# EbookReader.net
KiCad netlist of a schematic drawn in EAGLE
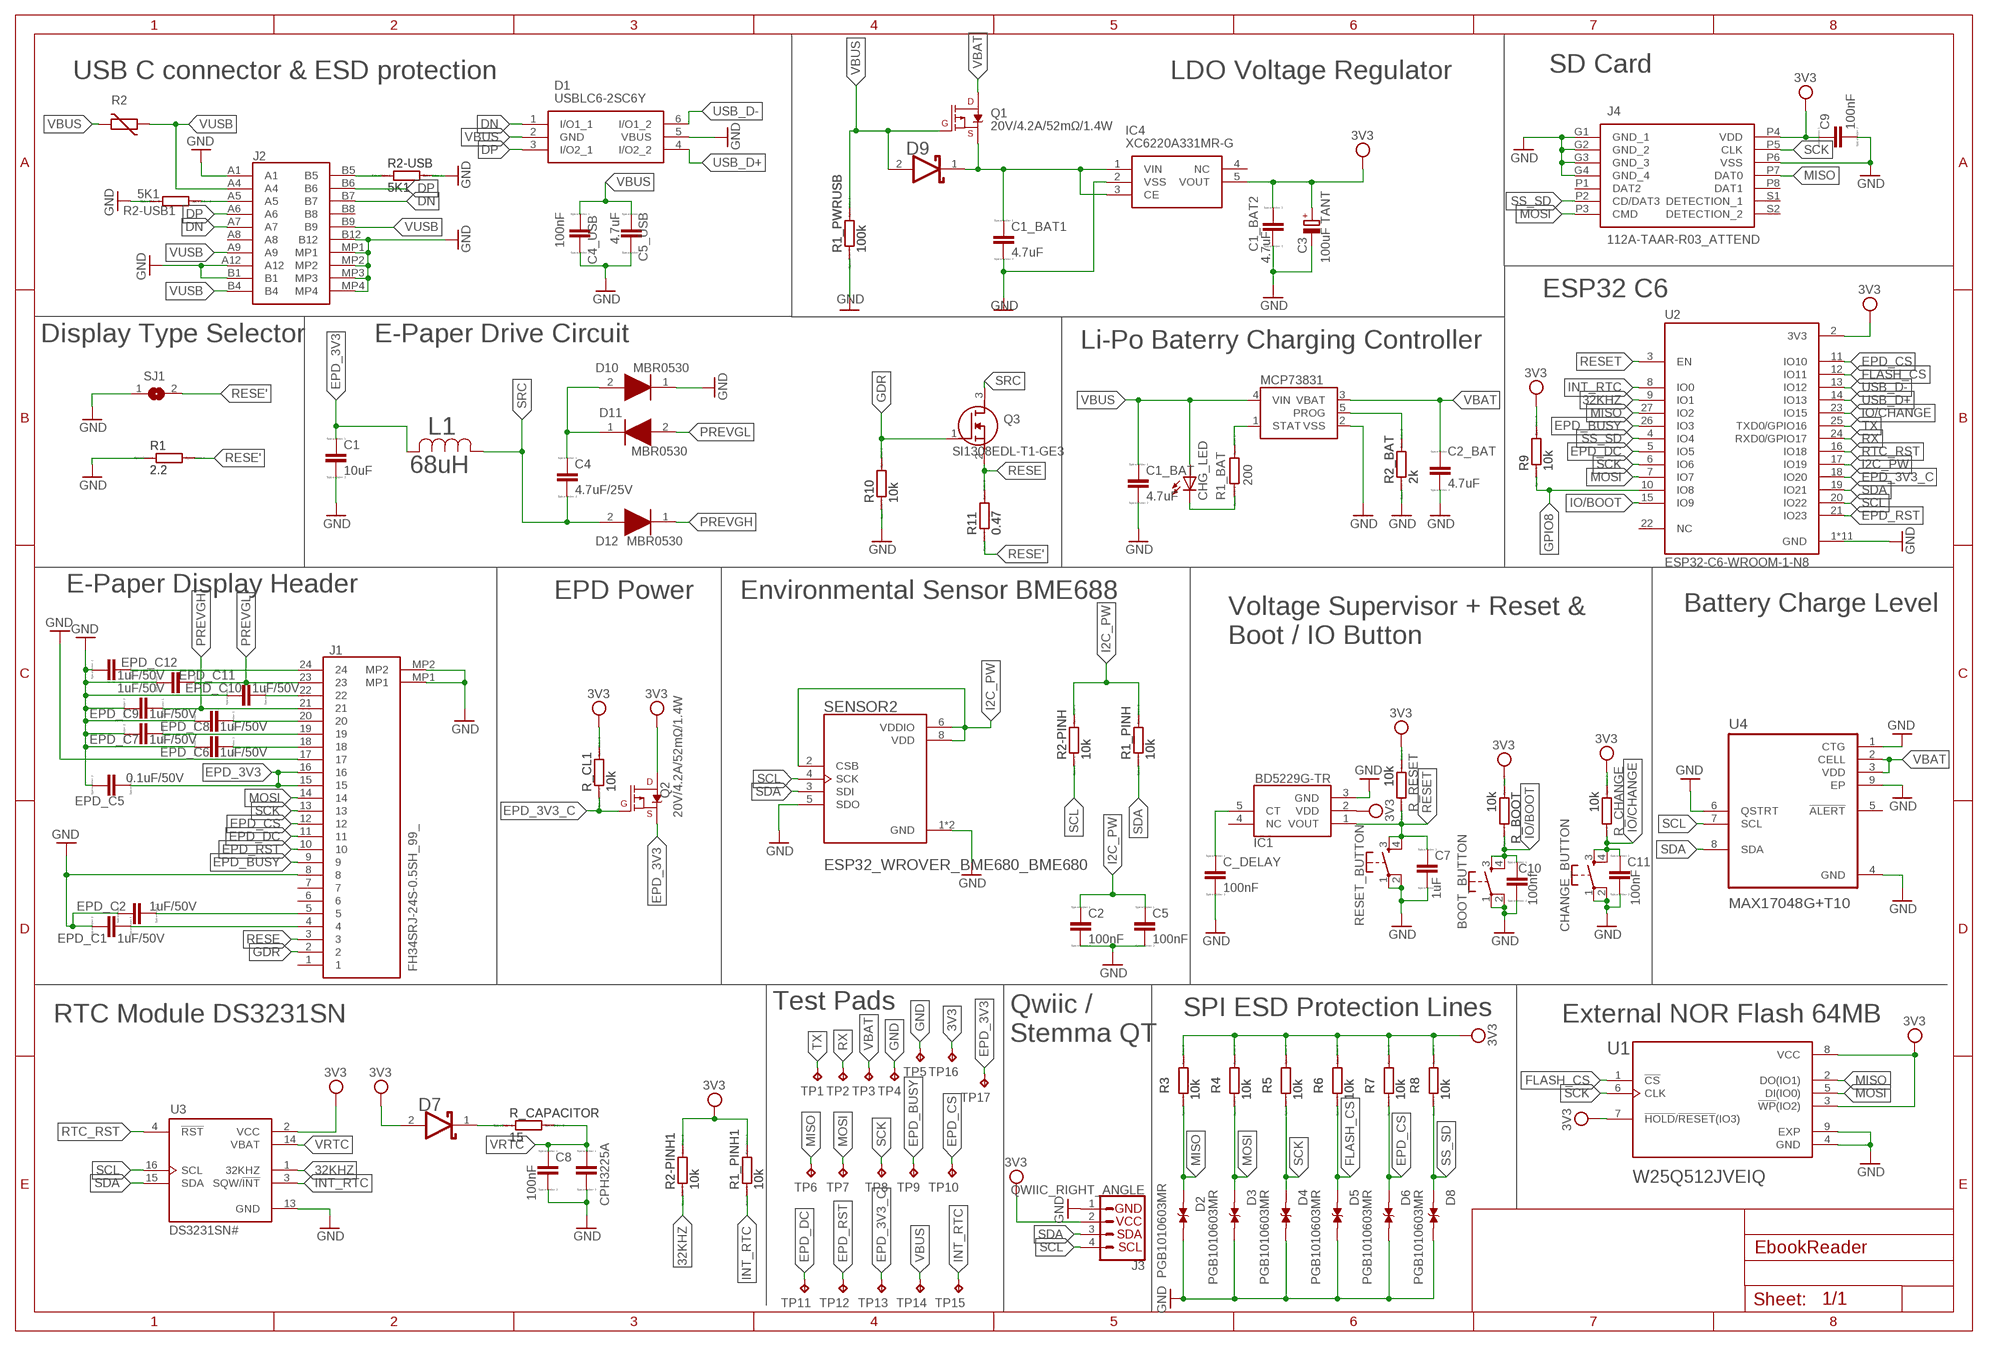
[diagram p0: schematic, sheet 1]

(export (version "E")
  (design (tool "Eeschema 10.0.6"))
  (components
    (comp (ref "BOOT_BUTTON")
      (value "BUTTON_CUSYOMV1")
      (footprint "eagle-import:MYBUTTON")
      (libsource (lib "eagle-import") (part "BUTTON_CUSYOMV1"))
    )
    (comp (ref "C1")
      (value "10uF")
      (footprint "eagle-import:ESP32_WROVER_EAGLE-LTSPICE_C0402")
      (libsource (lib "eagle-import") (part "ESP32_WROVER_EAGLE-LTSPICE_CC0402"))
    )
    (comp (ref "C1_BAT")
      (value "4.7uF")
      (footprint "eagle-import:ESP32_WROVER_EAGLE-LTSPICE_C0402")
      (libsource (lib "eagle-import") (part "ESP32_WROVER_EAGLE-LTSPICE_CC0402"))
    )
    (comp (ref "C1_BAT1")
      (value "4.7uF")
      (footprint "eagle-import:ESP32_WROVER_EAGLE-LTSPICE_C0402")
      (libsource (lib "eagle-import") (part "ESP32_WROVER_EAGLE-LTSPICE_CC0402"))
    )
    (comp (ref "C1_BAT2")
      (value "4.7uF")
      (footprint "eagle-import:ESP32_WROVER_EAGLE-LTSPICE_C0402")
      (libsource (lib "eagle-import") (part "ESP32_WROVER_EAGLE-LTSPICE_CC0402"))
    )
    (comp (ref "C2")
      (value "100nF")
      (footprint "eagle-import:ESP32_WROVER_EAGLE-LTSPICE_C0402")
      (libsource (lib "eagle-import") (part "ESP32_WROVER_EAGLE-LTSPICE_CC0402"))
    )
    (comp (ref "C2_BAT")
      (value "4.7uF")
      (footprint "eagle-import:ESP32_WROVER_EAGLE-LTSPICE_C0402")
      (libsource (lib "eagle-import") (part "ESP32_WROVER_EAGLE-LTSPICE_CC0402"))
    )
    (comp (ref "C3")
      (value "100uF TANT")
      (footprint "eagle-import:RCL_CT3528")
      (libsource (lib "eagle-import") (part "RCL_CPOL-EUCT3528"))
    )
    (comp (ref "C4")
      (value "4.7uF/25V")
      (footprint "eagle-import:ESP32_WROVER_EAGLE-LTSPICE_C0402")
      (libsource (lib "eagle-import") (part "ESP32_WROVER_EAGLE-LTSPICE_CC0402"))
    )
    (comp (ref "C4_USB")
      (value "100nF")
      (footprint "eagle-import:ESP32_WROVER_EAGLE-LTSPICE_C0402")
      (libsource (lib "eagle-import") (part "ESP32_WROVER_EAGLE-LTSPICE_CC0402"))
    )
    (comp (ref "C5")
      (value "100nF")
      (footprint "eagle-import:ESP32_WROVER_EAGLE-LTSPICE_C0402")
      (libsource (lib "eagle-import") (part "ESP32_WROVER_EAGLE-LTSPICE_CC0402"))
    )
    (comp (ref "C5_USB")
      (value "4.7uF")
      (footprint "eagle-import:ESP32_WROVER_EAGLE-LTSPICE_C0402")
      (libsource (lib "eagle-import") (part "ESP32_WROVER_EAGLE-LTSPICE_CC0402"))
    )
    (comp (ref "C7")
      (value "1uF")
      (footprint "eagle-import:ESP32_WROVER_EAGLE-LTSPICE_C0402")
      (libsource (lib "eagle-import") (part "ESP32_WROVER_EAGLE-LTSPICE_CC0402"))
    )
    (comp (ref "C8")
      (value "100nF")
      (footprint "eagle-import:EAGLE-LTSPICE_C0402")
      (libsource (lib "eagle-import") (part "EAGLE-LTSPICE_CC0402"))
    )
    (comp (ref "C9")
      (value "100nF")
      (footprint "eagle-import:ESP32_WROVER_EAGLE-LTSPICE_C0402")
      (libsource (lib "eagle-import") (part "ESP32_WROVER_EAGLE-LTSPICE_CC0402"))
    )
    (comp (ref "C10")
      (value "100nf")
      (footprint "eagle-import:ESP32_WROVER_EAGLE-LTSPICE_C0402")
      (libsource (lib "eagle-import") (part "ESP32_WROVER_EAGLE-LTSPICE_CC0402"))
    )
    (comp (ref "C11")
      (value "100nF")
      (footprint "eagle-import:ESP32_WROVER_EAGLE-LTSPICE_C0402")
      (libsource (lib "eagle-import") (part "ESP32_WROVER_EAGLE-LTSPICE_CC0402"))
    )
    (comp (ref "CHANGE_BUTTON")
      (value "BUTTON_CUSYOMV1")
      (footprint "eagle-import:MYBUTTON")
      (libsource (lib "eagle-import") (part "BUTTON_CUSYOMV1"))
    )
    (comp (ref "CHG_LED")
      (value "ADAFRUIT_LEDCHIP-LED0603")
      (footprint "eagle-import:ADAFRUIT_CHIP-LED0603")
      (libsource (lib "eagle-import") (part "ADAFRUIT_LEDCHIP-LED0603"))
    )
    (comp (ref "CPH3225A")
      (value "EAGLE-LTSPICE_CC0402")
      (footprint "eagle-import:EAGLE-LTSPICE_C0402")
      (libsource (lib "eagle-import") (part "EAGLE-LTSPICE_CC0402"))
    )
    (comp (ref "C_DELAY")
      (value "100nF")
      (footprint "eagle-import:ESP32_WROVER_EAGLE-LTSPICE_C0402")
      (libsource (lib "eagle-import") (part "ESP32_WROVER_EAGLE-LTSPICE_CC0402"))
    )
    (comp (ref "D1")
      (value "USBLC6-2SC6Y")
      (footprint "eagle-import:SOT95P280X145-6N")
      (fields (field (name "MF") "STMicroelectronics"))
      (libsource (lib "eagle-import") (part "USBLC6-2SC6Y"))
    )
    (comp (ref "D2")
      (value "PGB1010603MR")
      (footprint "eagle-import:DIOC1608X36N")
      (fields (field (name "MF") "Littelfuse Inc."))
      (libsource (lib "eagle-import") (part "PGB1010603MR"))
    )
    (comp (ref "D3")
      (value "PGB1010603MR")
      (footprint "eagle-import:DIOC1608X36N")
      (fields (field (name "MF") "Littelfuse Inc."))
      (libsource (lib "eagle-import") (part "PGB1010603MR"))
    )
    (comp (ref "D4")
      (value "PGB1010603MR")
      (footprint "eagle-import:DIOC1608X36N")
      (fields (field (name "MF") "Littelfuse Inc."))
      (libsource (lib "eagle-import") (part "PGB1010603MR"))
    )
    (comp (ref "D5")
      (value "PGB1010603MR")
      (footprint "eagle-import:DIOC1608X36N")
      (fields (field (name "MF") "Littelfuse Inc."))
      (libsource (lib "eagle-import") (part "PGB1010603MR"))
    )
    (comp (ref "D6")
      (value "PGB1010603MR")
      (footprint "eagle-import:DIOC1608X36N")
      (fields (field (name "MF") "Littelfuse Inc."))
      (libsource (lib "eagle-import") (part "PGB1010603MR"))
    )
    (comp (ref "D7")
      (value "ESP32_WROVER_AVX---SD0805S020S1R0_AVX_SD0805S020S1R0_0_0AVX_SD0805S020S1R0_0_0")
      (footprint "eagle-import:ESP32_WROVER_AVX---SD0805S020S1R0_AVX_SD0805S020S1R0_0")
      (fields
        (field (name "DIGIKEY_PART_NUMBER") "478-7800-1-ND")
        (field (name "MF") "AVX")
        (field (name "MOUSER_PART_NUMBER") "581-SD0805S020S1R0")
      )
      (libsource (lib "eagle-import") (part "ESP32_WROVER_AVX---SD0805S020S1R0_AVX_SD0805S020S1R0_0_0AVX_SD0805S020S1R0_0_0"))
    )
    (comp (ref "D8")
      (value "PGB1010603MR")
      (footprint "eagle-import:DIOC1608X36N")
      (fields (field (name "MF") "Littelfuse Inc."))
      (libsource (lib "eagle-import") (part "PGB1010603MR"))
    )
    (comp (ref "D9")
      (value "ESP32_WROVER_AVX---SD0805S020S1R0_AVX_SD0805S020S1R0_0_0AVX_SD0805S020S1R0_0_0")
      (footprint "eagle-import:ESP32_WROVER_AVX---SD0805S020S1R0_AVX_SD0805S020S1R0_0")
      (fields
        (field (name "DIGIKEY_PART_NUMBER") "478-7800-1-ND")
        (field (name "MF") "AVX")
        (field (name "MOUSER_PART_NUMBER") "581-SD0805S020S1R0")
      )
      (libsource (lib "eagle-import") (part "ESP32_WROVER_AVX---SD0805S020S1R0_AVX_SD0805S020S1R0_0_0AVX_SD0805S020S1R0_0_0"))
    )
    (comp (ref "D10")
      (value "MBR0530")
      (footprint "eagle-import:SOD3716X135N")
      (fields (field (name "MF") "ON Semiconductor"))
      (libsource (lib "eagle-import") (part "MBR0530"))
    )
    (comp (ref "D11")
      (value "MBR0530")
      (footprint "eagle-import:SOD3716X135N")
      (fields (field (name "MF") "ON Semiconductor"))
      (libsource (lib "eagle-import") (part "MBR0530"))
    )
    (comp (ref "D12")
      (value "MBR0530")
      (footprint "eagle-import:SOD3716X135N")
      (fields (field (name "MF") "ON Semiconductor"))
      (libsource (lib "eagle-import") (part "MBR0530"))
    )
    (comp (ref "EPD_C1")
      (value "1uF/50V")
      (footprint "eagle-import:EAGLE-LTSPICE_C0402")
      (libsource (lib "eagle-import") (part "EAGLE-LTSPICE_CC0402"))
    )
    (comp (ref "EPD_C2")
      (value "1uF/50V")
      (footprint "eagle-import:EAGLE-LTSPICE_C0402")
      (libsource (lib "eagle-import") (part "EAGLE-LTSPICE_CC0402"))
    )
    (comp (ref "EPD_C5")
      (value "0.1uF/50V")
      (footprint "eagle-import:EAGLE-LTSPICE_C0402")
      (libsource (lib "eagle-import") (part "EAGLE-LTSPICE_CC0402"))
    )
    (comp (ref "EPD_C6")
      (value "1uF/50V")
      (footprint "eagle-import:EAGLE-LTSPICE_C0402")
      (libsource (lib "eagle-import") (part "EAGLE-LTSPICE_CC0402"))
    )
    (comp (ref "EPD_C7")
      (value "1uF/50V")
      (footprint "eagle-import:EAGLE-LTSPICE_C0402")
      (libsource (lib "eagle-import") (part "EAGLE-LTSPICE_CC0402"))
    )
    (comp (ref "EPD_C8")
      (value "1uF/50V")
      (footprint "eagle-import:EAGLE-LTSPICE_C0402")
      (libsource (lib "eagle-import") (part "EAGLE-LTSPICE_CC0402"))
    )
    (comp (ref "EPD_C9")
      (value "1uF/50V")
      (footprint "eagle-import:EAGLE-LTSPICE_C0402")
      (libsource (lib "eagle-import") (part "EAGLE-LTSPICE_CC0402"))
    )
    (comp (ref "EPD_C10")
      (value "1uF/50V")
      (footprint "eagle-import:EAGLE-LTSPICE_C0402")
      (libsource (lib "eagle-import") (part "EAGLE-LTSPICE_CC0402"))
    )
    (comp (ref "EPD_C11")
      (value "1uF/50V")
      (footprint "eagle-import:EAGLE-LTSPICE_C0402")
      (libsource (lib "eagle-import") (part "EAGLE-LTSPICE_CC0402"))
    )
    (comp (ref "EPD_C12")
      (value "1uF/50V")
      (footprint "eagle-import:EAGLE-LTSPICE_C0402")
      (libsource (lib "eagle-import") (part "EAGLE-LTSPICE_CC0402"))
    )
    (comp (ref "IC1")
      (value "BD5229G-TR")
      (footprint "eagle-import:SOT95P280X125-5N")
      (fields (field (name "MOUSER_PART_NUMBER") "755-BD5229G-TR"))
      (libsource (lib "eagle-import") (part "BD5229G-TR"))
    )
    (comp (ref "IC4")
      (value "XC6220A331MR-G")
      (footprint "eagle-import:SOT95P280X120-5N")
      (fields (field (name "MOUSER_PART_NUMBER") "865-XC6220A331MR-G"))
      (libsource (lib "eagle-import") (part "XC6220A331MR-G"))
    )
    (comp (ref "J1")
      (value "FH34SRJ-24S-0.5SH_99_")
      (footprint "eagle-import:FH34SRJ24S05SH99")
      (fields
        (field (name "MANUFACTURER_PART_NUMBER") "FH34SRJ-24S-0.5SH(99)")
        (field (name "MOUSER_PART_NUMBER") "798-FH34SRJ24S05SH99")
      )
      (libsource (lib "eagle-import") (part "FH34SRJ-24S-0.5SH_99_"))
    )
    (comp (ref "J2")
      (value "SAMACSYS_PARTS_USB4110-GF-A")
      (footprint "eagle-import:SAMACSYS_PARTS_USB4110GFA")
      (fields
        (field (name "MANUFACTURER_PART_NUMBER") "USB4110-GF-A")
        (field (name "MOUSER_PART_NUMBER") "640-USB4110-GF-A")
      )
      (libsource (lib "eagle-import") (part "SAMACSYS_PARTS_USB4110-GF-A"))
    )
    (comp (ref "J3")
      (value "QWIIC_RIGHT_ANGLE")
      (footprint "eagle-import:JST04_1MM_RA")
      (libsource (lib "eagle-import") (part "QWIIC_CONNECTORJS-1MM"))
    )
    (comp (ref "J4")
      (value "112A-TAAR-R03_ATTEND")
      (footprint "eagle-import:112ATAARR03ATTEND")
      (fields (field (name "MANUFACTURER_PART_NUMBER") "112A-TAAR-R03 ATTEND"))
      (libsource (lib "eagle-import") (part "112A-TAAR-R03_ATTEND"))
    )
    (comp (ref "L1")
      (value "68uH")
      (footprint "eagle-import:IND_4828-WE-TPC_WRE")
      (fields
        (field (name "MANUFACTURER_PART_NUMBER") "744043680")
        (field (name "COPYRIGHT") "Copyright (C) 2024 Ultra Librarian. All rights reserved.")
      )
      (libsource (lib "eagle-import") (part "744043680IND_4828-WE-TPC_WRE"))
    )
    (comp (ref "MCP73831")
      (value "ESP32_WROVER_SPARKFUN-IC-POWER_MCP73831")
      (footprint "eagle-import:ESP32_WROVER_SPARKFUN-IC-POWER_SOT23-5")
      (libsource (lib "eagle-import") (part "ESP32_WROVER_SPARKFUN-IC-POWER_MCP73831"))
    )
    (comp (ref "Q1")
      (value "20V/4.2A/52mΩ/1.4W")
      (footprint "eagle-import:ESP32_WROVER_SPARKFUN-DISCRETESEMI_SOT23-3")
      (libsource (lib "eagle-import") (part "ESP32_WROVER_SPARKFUN-DISCRETESEMI_MOSFET_PCH-DMG2305UX-7"))
    )
    (comp (ref "Q2")
      (value "20V/4.2A/52mΩ/1.4W")
      (footprint "eagle-import:ESP32_WROVER_SPARKFUN-DISCRETESEMI_SOT23-3")
      (libsource (lib "eagle-import") (part "ESP32_WROVER_SPARKFUN-DISCRETESEMI_MOSFET_PCH-DMG2305UX-7"))
    )
    (comp (ref "Q3")
      (value "SI1308EDL-T1-GE3")
      (footprint "eagle-import:SOT65P210X110-3N")
      (fields (field (name "MF") "Vishay Siliconix"))
      (libsource (lib "eagle-import") (part "SI1308EDL-T1-GE3"))
    )
    (comp (ref "R1")
      (value "2.2")
      (footprint "eagle-import:ESP32_WROVER_EAGLE-LTSPICE_R0402")
      (libsource (lib "eagle-import") (part "ESP32_WROVER_EAGLE-LTSPICE_RR0402"))
    )
    (comp (ref "R1_BAT")
      (value "200")
      (footprint "eagle-import:ESP32_WROVER_EAGLE-LTSPICE_R0402")
      (libsource (lib "eagle-import") (part "ESP32_WROVER_EAGLE-LTSPICE_RR0402"))
    )
    (comp (ref "R1_PINH")
      (value "10k")
      (footprint "eagle-import:ESP32_WROVER_EAGLE-LTSPICE_R0402")
      (libsource (lib "eagle-import") (part "ESP32_WROVER_EAGLE-LTSPICE_RR0402"))
    )
    (comp (ref "R1_PINH1")
      (value "10k")
      (footprint "eagle-import:ESP32_WROVER_EAGLE-LTSPICE_R0402")
      (libsource (lib "eagle-import") (part "ESP32_WROVER_EAGLE-LTSPICE_RR0402"))
    )
    (comp (ref "R1_PWRUSB")
      (value "100k")
      (footprint "eagle-import:ESP32_WROVER_EAGLE-LTSPICE_R0402")
      (libsource (lib "eagle-import") (part "ESP32_WROVER_EAGLE-LTSPICE_RR0402"))
    )
    (comp (ref "R2")
      (value "ESP32C6_VARISTORCN1812")
      (footprint "eagle-import:ESP32C6_VARISTOR_CT_CN1812")
      (libsource (lib "eagle-import") (part "ESP32C6_VARISTORCN1812"))
    )
    (comp (ref "R2-PINH")
      (value "10k")
      (footprint "eagle-import:ESP32_WROVER_EAGLE-LTSPICE_R0402")
      (libsource (lib "eagle-import") (part "ESP32_WROVER_EAGLE-LTSPICE_RR0402"))
    )
    (comp (ref "R2-PINH1")
      (value "10k")
      (footprint "eagle-import:ESP32_WROVER_EAGLE-LTSPICE_R0402")
      (libsource (lib "eagle-import") (part "ESP32_WROVER_EAGLE-LTSPICE_RR0402"))
    )
    (comp (ref "R2-USB")
      (value "5K1")
      (footprint "eagle-import:ESP32_WROVER_EAGLE-LTSPICE_R0402")
      (libsource (lib "eagle-import") (part "ESP32_WROVER_EAGLE-LTSPICE_RR0402"))
    )
    (comp (ref "R2-USB1")
      (value "5K1")
      (footprint "eagle-import:ESP32_WROVER_EAGLE-LTSPICE_R0402")
      (libsource (lib "eagle-import") (part "ESP32_WROVER_EAGLE-LTSPICE_RR0402"))
    )
    (comp (ref "R2_BAT")
      (value "2k")
      (footprint "eagle-import:ESP32_WROVER_EAGLE-LTSPICE_R0402")
      (libsource (lib "eagle-import") (part "ESP32_WROVER_EAGLE-LTSPICE_RR0402"))
    )
    (comp (ref "R3")
      (value "10k")
      (footprint "eagle-import:ESP32_WROVER_EAGLE-LTSPICE_R0402")
      (libsource (lib "eagle-import") (part "ESP32_WROVER_EAGLE-LTSPICE_RR0402"))
    )
    (comp (ref "R4")
      (value "10k")
      (footprint "eagle-import:ESP32_WROVER_EAGLE-LTSPICE_R0402")
      (libsource (lib "eagle-import") (part "ESP32_WROVER_EAGLE-LTSPICE_RR0402"))
    )
    (comp (ref "R5")
      (value "10k")
      (footprint "eagle-import:ESP32_WROVER_EAGLE-LTSPICE_R0402")
      (libsource (lib "eagle-import") (part "ESP32_WROVER_EAGLE-LTSPICE_RR0402"))
    )
    (comp (ref "R6")
      (value "10k")
      (footprint "eagle-import:ESP32_WROVER_EAGLE-LTSPICE_R0402")
      (libsource (lib "eagle-import") (part "ESP32_WROVER_EAGLE-LTSPICE_RR0402"))
    )
    (comp (ref "R7")
      (value "10k")
      (footprint "eagle-import:ESP32_WROVER_EAGLE-LTSPICE_R0402")
      (libsource (lib "eagle-import") (part "ESP32_WROVER_EAGLE-LTSPICE_RR0402"))
    )
    (comp (ref "R8")
      (value "10k")
      (footprint "eagle-import:ESP32_WROVER_EAGLE-LTSPICE_R0402")
      (libsource (lib "eagle-import") (part "ESP32_WROVER_EAGLE-LTSPICE_RR0402"))
    )
    (comp (ref "R9")
      (value "10k")
      (footprint "eagle-import:ESP32_WROVER_EAGLE-LTSPICE_R0402")
      (libsource (lib "eagle-import") (part "ESP32_WROVER_EAGLE-LTSPICE_RR0402"))
    )
    (comp (ref "R10")
      (value "10k")
      (footprint "eagle-import:ESP32_WROVER_EAGLE-LTSPICE_R0402")
      (libsource (lib "eagle-import") (part "ESP32_WROVER_EAGLE-LTSPICE_RR0402"))
    )
    (comp (ref "R11")
      (value "0.47")
      (footprint "eagle-import:ESP32_WROVER_EAGLE-LTSPICE_R0402")
      (libsource (lib "eagle-import") (part "ESP32_WROVER_EAGLE-LTSPICE_RR0402"))
    )
    (comp (ref "RESET_BUTTON")
      (value "BUTTON_CUSYOMV1")
      (footprint "eagle-import:MYBUTTON")
      (libsource (lib "eagle-import") (part "BUTTON_CUSYOMV1"))
    )
    (comp (ref "R_BOOT")
      (value "10k")
      (footprint "eagle-import:ESP32_WROVER_EAGLE-LTSPICE_R0402")
      (libsource (lib "eagle-import") (part "ESP32_WROVER_EAGLE-LTSPICE_RR0402"))
    )
    (comp (ref "R_CAPACITOR")
      (value "15")
      (footprint "eagle-import:ESP32_WROVER_EAGLE-LTSPICE_R0402")
      (libsource (lib "eagle-import") (part "ESP32_WROVER_EAGLE-LTSPICE_RR0402"))
    )
    (comp (ref "R_CHANGE")
      (value "10k")
      (footprint "eagle-import:ESP32_WROVER_EAGLE-LTSPICE_R0402")
      (libsource (lib "eagle-import") (part "ESP32_WROVER_EAGLE-LTSPICE_RR0402"))
    )
    (comp (ref "R_CL1")
      (value "10k")
      (footprint "eagle-import:ESP32_WROVER_EAGLE-LTSPICE_R0402")
      (libsource (lib "eagle-import") (part "ESP32_WROVER_EAGLE-LTSPICE_RR0402"))
    )
    (comp (ref "R_RESET")
      (value "10k")
      (footprint "eagle-import:ESP32_WROVER_EAGLE-LTSPICE_R0402")
      (libsource (lib "eagle-import") (part "ESP32_WROVER_EAGLE-LTSPICE_RR0402"))
    )
    (comp (ref "SENSOR2")
      (value "ESP32_WROVER_BME680_BME680")
      (footprint "eagle-import:ESP32_WROVER_BME680_PSON80P300X300X100-8N")
      (fields (field (name "MF") "Bosch Sensortec") (field (name "MP") "BME680"))
      (libsource (lib "eagle-import") (part "ESP32_WROVER_BME680_BME680"))
    )
    (comp (ref "SJ1") (value "SJ") (footprint "eagle-import:SJ") (libsource (lib "eagle-import") (part "SJ")))
    (comp (ref "TP1")
      (value "TPTP20R")
      (footprint "eagle-import:TP20R")
      (libsource (lib "eagle-import") (part "TPTP20R"))
    )
    (comp (ref "TP2")
      (value "TPTP20R")
      (footprint "eagle-import:TP20R")
      (libsource (lib "eagle-import") (part "TPTP20R"))
    )
    (comp (ref "TP3")
      (value "TPTP20R")
      (footprint "eagle-import:TP20R")
      (libsource (lib "eagle-import") (part "TPTP20R"))
    )
    (comp (ref "TP4")
      (value "TPTP20R")
      (footprint "eagle-import:TP20R")
      (libsource (lib "eagle-import") (part "TPTP20R"))
    )
    (comp (ref "TP5")
      (value "TPTP20R")
      (footprint "eagle-import:TP20R")
      (libsource (lib "eagle-import") (part "TPTP20R"))
    )
    (comp (ref "TP6")
      (value "TPTP20R")
      (footprint "eagle-import:TP20R")
      (libsource (lib "eagle-import") (part "TPTP20R"))
    )
    (comp (ref "TP7")
      (value "TPTP20R")
      (footprint "eagle-import:TP20R")
      (libsource (lib "eagle-import") (part "TPTP20R"))
    )
    (comp (ref "TP8")
      (value "TPTP20R")
      (footprint "eagle-import:TP20R")
      (libsource (lib "eagle-import") (part "TPTP20R"))
    )
    (comp (ref "TP9")
      (value "TPTP20R")
      (footprint "eagle-import:TP20R")
      (libsource (lib "eagle-import") (part "TPTP20R"))
    )
    (comp (ref "TP10")
      (value "TPTP20R")
      (footprint "eagle-import:TP20R")
      (libsource (lib "eagle-import") (part "TPTP20R"))
    )
    (comp (ref "TP11")
      (value "TPTP20R")
      (footprint "eagle-import:TP20R")
      (libsource (lib "eagle-import") (part "TPTP20R"))
    )
    (comp (ref "TP12")
      (value "TPTP20R")
      (footprint "eagle-import:TP20R")
      (libsource (lib "eagle-import") (part "TPTP20R"))
    )
    (comp (ref "TP13")
      (value "TPTP20R")
      (footprint "eagle-import:TP20R")
      (libsource (lib "eagle-import") (part "TPTP20R"))
    )
    (comp (ref "TP14")
      (value "TPTP20R")
      (footprint "eagle-import:TP20R")
      (libsource (lib "eagle-import") (part "TPTP20R"))
    )
    (comp (ref "TP15")
      (value "TPTP20R")
      (footprint "eagle-import:TP20R")
      (libsource (lib "eagle-import") (part "TPTP20R"))
    )
    (comp (ref "TP16")
      (value "TPTP20R")
      (footprint "eagle-import:TP20R")
      (libsource (lib "eagle-import") (part "TPTP20R"))
    )
    (comp (ref "TP17")
      (value "TPTP20R")
      (footprint "eagle-import:TP20R")
      (libsource (lib "eagle-import") (part "TPTP20R"))
    )
    (comp (ref "U1")
      (value "W25Q512JVEIQ")
      (footprint "eagle-import:SON127P600X800X80-9N")
      (fields (field (name "MF") "Winbond Electronics"))
      (libsource (lib "eagle-import") (part "W25Q512JVEIQ"))
    )
    (comp (ref "U2")
      (value "ESP32-C6-WROOM-1-N8")
      (footprint "eagle-import:XCVR_ESP32-C6-WROOM-1-N8")
      (fields (field (name "MF") "Espressif Systems"))
      (libsource (lib "eagle-import") (part "ESP32-C6-WROOM-1-N8"))
    )
    (comp (ref "U3")
      (value "DS3231SN#")
      (footprint "eagle-import:SOIC127P1032X265-16N")
      (fields (field (name "MF") "Analog Devices"))
      (libsource (lib "eagle-import") (part "DS3231SN#"))
    )
    (comp (ref "U4")
      (value "MAX17048G+T10")
      (footprint "eagle-import:SON50P200X200X80-9N")
      (fields (field (name "MF") "Analog Devices"))
      (libsource (lib "eagle-import") (part "MAX17048G+T10"))
    )
  )
  (nets
    (net (code "1") (name "3V3") (class "Default")
      (node (ref "C1_BAT2") (pin "1") (pinfunction "1_1") (pintype "passive"))
      (node (ref "C3") (pin "+") (pinfunction "+_+") (pintype "passive"))
      (node (ref "C9") (pin "1") (pinfunction "1_1") (pintype "passive"))
      (node (ref "D7") (pin "2") (pinfunction "ANODE_2") (pintype "bidirectional"))
      (node (ref "IC1") (pin "2") (pinfunction "VDD_2") (pintype "bidirectional"))
      (node (ref "IC4") (pin "5") (pinfunction "VOUT_5") (pintype "bidirectional"))
      (node (ref "J3") (pin "2") (pinfunction "2_2") (pintype "power_in"))
      (node (ref "J4") (pin "P4") (pinfunction "VDD_P4") (pintype "bidirectional"))
      (node (ref "Q2") (pin "3") (pinfunction "D_3") (pintype "bidirectional"))
      (node (ref "R1_PINH1") (pin "2") (pinfunction "2_2") (pintype "passive"))
      (node (ref "R2-PINH1") (pin "2") (pinfunction "2_2") (pintype "passive"))
      (node (ref "R3") (pin "2") (pinfunction "2_2") (pintype "passive"))
      (node (ref "R4") (pin "2") (pinfunction "2_2") (pintype "passive"))
      (node (ref "R5") (pin "2") (pinfunction "2_2") (pintype "passive"))
      (node (ref "R6") (pin "2") (pinfunction "2_2") (pintype "passive"))
      (node (ref "R7") (pin "2") (pinfunction "2_2") (pintype "passive"))
      (node (ref "R8") (pin "2") (pinfunction "2_2") (pintype "passive"))
      (node (ref "R9") (pin "2") (pinfunction "2_2") (pintype "passive"))
      (node (ref "R_BOOT") (pin "1") (pinfunction "1_1") (pintype "passive"))
      (node (ref "R_CHANGE") (pin "1") (pinfunction "1_1") (pintype "passive"))
      (node (ref "R_CL1") (pin "2") (pinfunction "2_2") (pintype "passive"))
      (node (ref "R_RESET") (pin "1") (pinfunction "1_1") (pintype "passive"))
      (node (ref "TP16") (pin "TP") (pinfunction "TP_TP") (pintype "input"))
      (node (ref "U1") (pin "3") (pinfunction "~{WP}(IO2)_3") (pintype "bidirectional"))
      (node (ref "U1") (pin "7") (pinfunction "~{HOLD}/~{RESET}(IO3)_7") (pintype "bidirectional"))
      (node (ref "U1") (pin "8") (pinfunction "VCC_8") (pintype "power_in"))
      (node (ref "U2") (pin "2") (pinfunction "3V3_2") (pintype "power_in"))
      (node (ref "U3") (pin "2") (pinfunction "VCC_2") (pintype "power_in"))
    )
    (net (code "2") (name "32KHZ") (class "Default")
      (node (ref "R2-PINH1") (pin "1") (pinfunction "1_1") (pintype "passive"))
      (node (ref "U2") (pin "9") (pinfunction "IO1_9") (pintype "bidirectional"))
      (node (ref "U3") (pin "1") (pinfunction "32KHZ_1") (pintype "output"))
    )
    (net (code "3") (name "DN") (class "Default")
      (node (ref "D1") (pin "1") (pinfunction "I/O1_1_1") (pintype "bidirectional"))
      (node (ref "J2") (pin "A7") (pinfunction "A7_A7") (pintype "bidirectional"))
      (node (ref "J2") (pin "B7") (pinfunction "B7_B7") (pintype "bidirectional"))
    )
    (net (code "4") (name "DP") (class "Default")
      (node (ref "D1") (pin "3") (pinfunction "I/O2_1_3") (pintype "bidirectional"))
      (node (ref "J2") (pin "A6") (pinfunction "A6_A6") (pintype "bidirectional"))
      (node (ref "J2") (pin "B6") (pinfunction "B6_B6") (pintype "bidirectional"))
    )
    (net (code "5") (name "EPD_3V3") (class "Default")
      (node (ref "C1") (pin "1") (pinfunction "1_1") (pintype "passive"))
      (node (ref "EPD_C5") (pin "1") (pinfunction "1_1") (pintype "passive"))
      (node (ref "J1") (pin "15") (pinfunction "15_15") (pintype "bidirectional"))
      (node (ref "J1") (pin "16") (pinfunction "16_16") (pintype "bidirectional"))
      (node (ref "L1") (pin "2") (pinfunction "2_2") (pintype "passive"))
      (node (ref "Q2") (pin "2") (pinfunction "S_2") (pintype "bidirectional"))
      (node (ref "TP17") (pin "TP") (pinfunction "TP_TP") (pintype "input"))
    )
    (net (code "6") (name "EPD_3V3_C") (class "Default")
      (node (ref "Q2") (pin "1") (pinfunction "G_1") (pintype "bidirectional"))
      (node (ref "R_CL1") (pin "1") (pinfunction "1_1") (pintype "passive"))
      (node (ref "TP13") (pin "TP") (pinfunction "TP_TP") (pintype "input"))
      (node (ref "U2") (pin "18") (pinfunction "IO20_18") (pintype "bidirectional"))
    )
    (net (code "7") (name "EPD_BUSY") (class "Default")
      (node (ref "J1") (pin "9") (pinfunction "9_9") (pintype "bidirectional"))
      (node (ref "TP9") (pin "TP") (pinfunction "TP_TP") (pintype "input"))
      (node (ref "U2") (pin "26") (pinfunction "IO3_26") (pintype "bidirectional"))
    )
    (net (code "8") (name "EPD_CS") (class "Default")
      (node (ref "D6") (pin "1") (pinfunction "1_1") (pintype "passive"))
      (node (ref "J1") (pin "12") (pinfunction "12_12") (pintype "bidirectional"))
      (node (ref "R7") (pin "1") (pinfunction "1_1") (pintype "passive"))
      (node (ref "TP10") (pin "TP") (pinfunction "TP_TP") (pintype "input"))
      (node (ref "U2") (pin "11") (pinfunction "IO10_11") (pintype "bidirectional"))
    )
    (net (code "9") (name "EPD_DC") (class "Default")
      (node (ref "J1") (pin "11") (pinfunction "11_11") (pintype "bidirectional"))
      (node (ref "TP11") (pin "TP") (pinfunction "TP_TP") (pintype "input"))
      (node (ref "U2") (pin "5") (pinfunction "IO5_5") (pintype "bidirectional"))
    )
    (net (code "10") (name "EPD_RST") (class "Default")
      (node (ref "J1") (pin "10") (pinfunction "10_10") (pintype "bidirectional"))
      (node (ref "TP12") (pin "TP") (pinfunction "TP_TP") (pintype "input"))
      (node (ref "U2") (pin "21") (pinfunction "IO23_21") (pintype "bidirectional"))
    )
    (net (code "11") (name "FLASH_CS") (class "Default")
      (node (ref "D5") (pin "1") (pinfunction "1_1") (pintype "passive"))
      (node (ref "R6") (pin "1") (pinfunction "1_1") (pintype "passive"))
      (node (ref "U1") (pin "1") (pinfunction "~{CS}_1") (pintype "input"))
      (node (ref "U2") (pin "12") (pinfunction "IO11_12") (pintype "bidirectional"))
    )
    (net (code "12") (name "GDR") (class "Default")
      (node (ref "J1") (pin "2") (pinfunction "2_2") (pintype "bidirectional"))
      (node (ref "Q3") (pin "1") (pinfunction "G_1") (pintype "bidirectional"))
      (node (ref "R10") (pin "2") (pinfunction "2_2") (pintype "passive"))
    )
    (net (code "13") (name "GND") (class "Default")
      (node (ref "BOOT_BUTTON") (pin "1") (pinfunction "1_1") (pintype "passive"))
      (node (ref "BOOT_BUTTON") (pin "2") (pinfunction "2_2") (pintype "passive"))
      (node (ref "C1") (pin "2") (pinfunction "2_2") (pintype "passive"))
      (node (ref "C10") (pin "2") (pinfunction "2_2") (pintype "passive"))
      (node (ref "C11") (pin "2") (pinfunction "2_2") (pintype "passive"))
      (node (ref "C1_BAT") (pin "2") (pinfunction "2_2") (pintype "passive"))
      (node (ref "C1_BAT1") (pin "2") (pinfunction "2_2") (pintype "passive"))
      (node (ref "C1_BAT2") (pin "2") (pinfunction "2_2") (pintype "passive"))
      (node (ref "C2") (pin "2") (pinfunction "2_2") (pintype "passive"))
      (node (ref "C2_BAT") (pin "2") (pinfunction "2_2") (pintype "passive"))
      (node (ref "C3") (pin "-") (pinfunction "-_-") (pintype "passive"))
      (node (ref "C4_USB") (pin "2") (pinfunction "2_2") (pintype "passive"))
      (node (ref "C5") (pin "2") (pinfunction "2_2") (pintype "passive"))
      (node (ref "C5_USB") (pin "2") (pinfunction "2_2") (pintype "passive"))
      (node (ref "C7") (pin "2") (pinfunction "2_2") (pintype "passive"))
      (node (ref "C8") (pin "2") (pinfunction "2_2") (pintype "passive"))
      (node (ref "C9") (pin "2") (pinfunction "2_2") (pintype "passive"))
      (node (ref "CHANGE_BUTTON") (pin "1") (pinfunction "1_1") (pintype "passive"))
      (node (ref "CHANGE_BUTTON") (pin "2") (pinfunction "2_2") (pintype "passive"))
      (node (ref "CPH3225A") (pin "2") (pinfunction "2_2") (pintype "passive"))
      (node (ref "C_DELAY") (pin "2") (pinfunction "2_2") (pintype "passive"))
      (node (ref "D1") (pin "5") (pinfunction "VBUS_5") (pintype "bidirectional"))
      (node (ref "D10") (pin "1") (pinfunction "K_1") (pintype "bidirectional"))
      (node (ref "D2") (pin "2") (pinfunction "2_2") (pintype "passive"))
      (node (ref "D3") (pin "2") (pinfunction "2_2") (pintype "passive"))
      (node (ref "D4") (pin "2") (pinfunction "2_2") (pintype "passive"))
      (node (ref "D5") (pin "2") (pinfunction "2_2") (pintype "passive"))
      (node (ref "D6") (pin "2") (pinfunction "2_2") (pintype "passive"))
      (node (ref "D8") (pin "2") (pinfunction "2_2") (pintype "passive"))
      (node (ref "EPD_C1") (pin "2") (pinfunction "2_2") (pintype "passive"))
      (node (ref "EPD_C10") (pin "2") (pinfunction "2_2") (pintype "passive"))
      (node (ref "EPD_C11") (pin "2") (pinfunction "2_2") (pintype "passive"))
      (node (ref "EPD_C12") (pin "2") (pinfunction "2_2") (pintype "passive"))
      (node (ref "EPD_C2") (pin "2") (pinfunction "2_2") (pintype "passive"))
      (node (ref "EPD_C5") (pin "2") (pinfunction "2_2") (pintype "passive"))
      (node (ref "EPD_C6") (pin "2") (pinfunction "2_2") (pintype "passive"))
      (node (ref "EPD_C7") (pin "2") (pinfunction "2_2") (pintype "passive"))
      (node (ref "EPD_C8") (pin "2") (pinfunction "2_2") (pintype "passive"))
      (node (ref "EPD_C9") (pin "2") (pinfunction "2_2") (pintype "passive"))
      (node (ref "IC1") (pin "3") (pinfunction "GND_3") (pintype "bidirectional"))
      (node (ref "IC4") (pin "2") (pinfunction "VSS_2") (pintype "bidirectional"))
      (node (ref "J1") (pin "17") (pinfunction "17_17") (pintype "bidirectional"))
      (node (ref "J1") (pin "8") (pinfunction "8_8") (pintype "bidirectional"))
      (node (ref "J1") (pin "MP1") (pinfunction "MP1_MP1") (pintype "bidirectional"))
      (node (ref "J1") (pin "MP2") (pinfunction "MP2_MP2") (pintype "bidirectional"))
      (node (ref "J2") (pin "A1") (pinfunction "A1_A1") (pintype "bidirectional"))
      (node (ref "J2") (pin "A12") (pinfunction "A12_A12") (pintype "bidirectional"))
      (node (ref "J2") (pin "B1") (pinfunction "B1_B1") (pintype "bidirectional"))
      (node (ref "J2") (pin "B12") (pinfunction "B12_B12") (pintype "bidirectional"))
      (node (ref "J2") (pin "MP1") (pinfunction "MP1_MP1") (pintype "bidirectional"))
      (node (ref "J2") (pin "MP2") (pinfunction "MP2_MP2") (pintype "bidirectional"))
      (node (ref "J2") (pin "MP3") (pinfunction "MP3_MP3") (pintype "bidirectional"))
      (node (ref "J2") (pin "MP4") (pinfunction "MP4_MP4") (pintype "bidirectional"))
      (node (ref "J3") (pin "1") (pinfunction "1_1") (pintype "power_in"))
      (node (ref "J4") (pin "G1") (pinfunction "GND_1_G1") (pintype "bidirectional"))
      (node (ref "J4") (pin "G2") (pinfunction "GND_2_G2") (pintype "bidirectional"))
      (node (ref "J4") (pin "G3") (pinfunction "GND_3_G3") (pintype "bidirectional"))
      (node (ref "J4") (pin "G4") (pinfunction "GND_4_G4") (pintype "bidirectional"))
      (node (ref "J4") (pin "P6") (pinfunction "VSS_P6") (pintype "bidirectional"))
      (node (ref "MCP73831") (pin "2") (pinfunction "VSS_2") (pintype "power_in"))
      (node (ref "R1") (pin "1") (pinfunction "1_1") (pintype "passive"))
      (node (ref "R10") (pin "1") (pinfunction "1_1") (pintype "passive"))
      (node (ref "R1_PWRUSB") (pin "1") (pinfunction "1_1") (pintype "passive"))
      (node (ref "R2-USB") (pin "2") (pinfunction "2_2") (pintype "passive"))
      (node (ref "R2-USB1") (pin "1") (pinfunction "1_1") (pintype "passive"))
      (node (ref "R2_BAT") (pin "1") (pinfunction "1_1") (pintype "passive"))
      (node (ref "RESET_BUTTON") (pin "1") (pinfunction "1_1") (pintype "passive"))
      (node (ref "RESET_BUTTON") (pin "2") (pinfunction "2_2") (pintype "passive"))
      (node (ref "SENSOR2") (pin "1") (pinfunction "GND_1") (pintype "power_in"))
      (node (ref "SENSOR2") (pin "5") (pinfunction "SDO_5") (pintype "bidirectional"))
      (node (ref "SENSOR2") (pin "7") (pinfunction "GND_7") (pintype "power_in"))
      (node (ref "SJ1") (pin "1") (pinfunction "1_1") (pintype "passive"))
      (node (ref "TP4") (pin "TP") (pinfunction "TP_TP") (pintype "input"))
      (node (ref "TP5") (pin "TP") (pinfunction "TP_TP") (pintype "input"))
      (node (ref "U1") (pin "4") (pinfunction "GND_4") (pintype "power_in"))
      (node (ref "U1") (pin "9") (pinfunction "EXP_9") (pintype "passive"))
      (node (ref "U2") (pin "1") (pinfunction "GND_1") (pintype "power_in"))
      (node (ref "U2") (pin "28") (pinfunction "GND_28") (pintype "power_in"))
      (node (ref "U2") (pin "29_1") (pinfunction "GND_29_1") (pintype "power_in"))
      (node (ref "U2") (pin "29_2") (pinfunction "GND_29_2") (pintype "power_in"))
      (node (ref "U2") (pin "29_3") (pinfunction "GND_29_3") (pintype "power_in"))
      (node (ref "U2") (pin "29_4") (pinfunction "GND_29_4") (pintype "power_in"))
      (node (ref "U2") (pin "29_5") (pinfunction "GND_29_5") (pintype "power_in"))
      (node (ref "U2") (pin "29_6") (pinfunction "GND_29_6") (pintype "power_in"))
      (node (ref "U2") (pin "29_7") (pinfunction "GND_29_7") (pintype "power_in"))
      (node (ref "U2") (pin "29_8") (pinfunction "GND_29_8") (pintype "power_in"))
      (node (ref "U2") (pin "29_9") (pinfunction "GND_29_9") (pintype "power_in"))
      (node (ref "U3") (pin "13") (pinfunction "GND_13") (pintype "power_in"))
      (node (ref "U4") (pin "1") (pinfunction "CTG_1") (pintype "power_in"))
      (node (ref "U4") (pin "4") (pinfunction "GND_4") (pintype "power_in"))
      (node (ref "U4") (pin "6") (pinfunction "QSTRT_6") (pintype "input"))
      (node (ref "U4") (pin "9") (pinfunction "EP_9") (pintype "power_in"))
    )
    (net (code "14") (name "GPIO8") (class "Default")
      (node (ref "R9") (pin "1") (pinfunction "1_1") (pintype "passive"))
      (node (ref "U2") (pin "10") (pinfunction "IO8_10") (pintype "bidirectional"))
    )
    (net (code "15") (name "I2C_PW") (class "Default")
      (node (ref "C2") (pin "1") (pinfunction "1_1") (pintype "passive"))
      (node (ref "C5") (pin "1") (pinfunction "1_1") (pintype "passive"))
      (node (ref "R1_PINH") (pin "2") (pinfunction "2_2") (pintype "passive"))
      (node (ref "R2-PINH") (pin "2") (pinfunction "2_2") (pintype "passive"))
      (node (ref "SENSOR2") (pin "2") (pinfunction "CSB_2") (pintype "input"))
      (node (ref "SENSOR2") (pin "6") (pinfunction "VDDIO_6") (pintype "power_in"))
      (node (ref "SENSOR2") (pin "8") (pinfunction "VDD_8") (pintype "power_in"))
      (node (ref "U2") (pin "17") (pinfunction "IO19_17") (pintype "bidirectional"))
    )
    (net (code "16") (name "INT_RTC") (class "Default")
      (node (ref "R1_PINH1") (pin "1") (pinfunction "1_1") (pintype "passive"))
      (node (ref "TP15") (pin "TP") (pinfunction "TP_TP") (pintype "input"))
      (node (ref "U2") (pin "8") (pinfunction "IO0_8") (pintype "bidirectional"))
      (node (ref "U3") (pin "3") (pinfunction "SQW/~{INT}_3") (pintype "output"))
    )
    (net (code "17") (name "IO{slash}BOOT") (class "Default")
      (node (ref "BOOT_BUTTON") (pin "3") (pinfunction "3_3") (pintype "passive"))
      (node (ref "BOOT_BUTTON") (pin "4") (pinfunction "4_4") (pintype "passive"))
      (node (ref "C10") (pin "1") (pinfunction "1_1") (pintype "passive"))
      (node (ref "R_BOOT") (pin "2") (pinfunction "2_2") (pintype "passive"))
      (node (ref "U2") (pin "15") (pinfunction "IO9_15") (pintype "bidirectional"))
    )
    (net (code "18") (name "IO{slash}CHANGE") (class "Default")
      (node (ref "C11") (pin "1") (pinfunction "1_1") (pintype "passive"))
      (node (ref "CHANGE_BUTTON") (pin "3") (pinfunction "3_3") (pintype "passive"))
      (node (ref "CHANGE_BUTTON") (pin "4") (pinfunction "4_4") (pintype "passive"))
      (node (ref "R_CHANGE") (pin "2") (pinfunction "2_2") (pintype "passive"))
      (node (ref "U2") (pin "23") (pinfunction "IO15_23") (pintype "bidirectional"))
    )
    (net (code "19") (name "MISO") (class "Default")
      (node (ref "D2") (pin "1") (pinfunction "1_1") (pintype "passive"))
      (node (ref "J4") (pin "P7") (pinfunction "DAT0_P7") (pintype "bidirectional"))
      (node (ref "R3") (pin "1") (pinfunction "1_1") (pintype "passive"))
      (node (ref "TP6") (pin "TP") (pinfunction "TP_TP") (pintype "input"))
      (node (ref "U1") (pin "2") (pinfunction "DO(IO1)_2") (pintype "bidirectional"))
      (node (ref "U2") (pin "27") (pinfunction "IO2_27") (pintype "bidirectional"))
    )
    (net (code "20") (name "MOSI") (class "Default")
      (node (ref "D3") (pin "1") (pinfunction "1_1") (pintype "passive"))
      (node (ref "J1") (pin "14") (pinfunction "14_14") (pintype "bidirectional"))
      (node (ref "J4") (pin "P3") (pinfunction "CMD_P3") (pintype "bidirectional"))
      (node (ref "R4") (pin "1") (pinfunction "1_1") (pintype "passive"))
      (node (ref "TP7") (pin "TP") (pinfunction "TP_TP") (pintype "input"))
      (node (ref "U1") (pin "5") (pinfunction "DI(IO0)_5") (pintype "bidirectional"))
      (node (ref "U2") (pin "7") (pinfunction "IO7_7") (pintype "bidirectional"))
    )
    (net (code "21") (name "Net-(CHG_LED-PadC)") (class "Default")
      (node (ref "CHG_LED") (pin "C") (pinfunction "C_C") (pintype "passive"))
      (node (ref "R1_BAT") (pin "2") (pinfunction "2_2") (pintype "passive"))
    )
    (net (code "22") (name "Net-(D7-CATHODE)") (class "Default")
      (node (ref "D7") (pin "1") (pinfunction "CATHODE_1") (pintype "bidirectional"))
      (node (ref "R_CAPACITOR") (pin "1") (pinfunction "1_1") (pintype "passive"))
    )
    (net (code "23") (name "Net-(D9-CATHODE)") (class "Default")
      (node (ref "C1_BAT1") (pin "1") (pinfunction "1_1") (pintype "passive"))
      (node (ref "D9") (pin "1") (pinfunction "CATHODE_1") (pintype "bidirectional"))
      (node (ref "IC4") (pin "1") (pinfunction "VIN_1") (pintype "bidirectional"))
      (node (ref "IC4") (pin "3") (pinfunction "CE_3") (pintype "bidirectional"))
      (node (ref "Q1") (pin "2") (pinfunction "S_2") (pintype "bidirectional"))
    )
    (net (code "24") (name "Net-(D10-A)") (class "Default")
      (node (ref "C4") (pin "1") (pinfunction "1_1") (pintype "passive"))
      (node (ref "D10") (pin "2") (pinfunction "A_2") (pintype "bidirectional"))
      (node (ref "D11") (pin "1") (pinfunction "K_1") (pintype "bidirectional"))
    )
    (net (code "25") (name "Net-(EPD_C1-Pad1)") (class "Default")
      (node (ref "EPD_C1") (pin "1") (pinfunction "1_1") (pintype "passive"))
      (node (ref "J1") (pin "4") (pinfunction "4_4") (pintype "bidirectional"))
    )
    (net (code "26") (name "Net-(EPD_C2-Pad1)") (class "Default")
      (node (ref "EPD_C2") (pin "1") (pinfunction "1_1") (pintype "passive"))
      (node (ref "J1") (pin "5") (pinfunction "5_5") (pintype "bidirectional"))
    )
    (net (code "27") (name "Net-(EPD_C6-Pad1)") (class "Default")
      (node (ref "EPD_C6") (pin "1") (pinfunction "1_1") (pintype "passive"))
      (node (ref "J1") (pin "18") (pinfunction "18_18") (pintype "bidirectional"))
    )
    (net (code "28") (name "Net-(EPD_C7-Pad1)") (class "Default")
      (node (ref "EPD_C7") (pin "1") (pinfunction "1_1") (pintype "passive"))
      (node (ref "J1") (pin "19") (pinfunction "19_19") (pintype "bidirectional"))
    )
    (net (code "29") (name "Net-(EPD_C8-Pad1)") (class "Default")
      (node (ref "EPD_C8") (pin "1") (pinfunction "1_1") (pintype "passive"))
      (node (ref "J1") (pin "20") (pinfunction "20_20") (pintype "bidirectional"))
    )
    (net (code "30") (name "Net-(EPD_C10-Pad1)") (class "Default")
      (node (ref "EPD_C10") (pin "1") (pinfunction "1_1") (pintype "passive"))
      (node (ref "J1") (pin "22") (pinfunction "22_22") (pintype "bidirectional"))
    )
    (net (code "31") (name "Net-(EPD_C12-Pad1)") (class "Default")
      (node (ref "EPD_C12") (pin "1") (pinfunction "1_1") (pintype "passive"))
      (node (ref "J1") (pin "24") (pinfunction "24_24") (pintype "bidirectional"))
    )
    (net (code "32") (name "Net-(IC1-CT)") (class "Default")
      (node (ref "C_DELAY") (pin "1") (pinfunction "1_1") (pintype "passive"))
      (node (ref "IC1") (pin "5") (pinfunction "CT_5") (pintype "bidirectional"))
    )
    (net (code "33") (name "Net-(J2-PadA5)") (class "Default")
      (node (ref "J2") (pin "A5") (pinfunction "A5_A5") (pintype "bidirectional"))
      (node (ref "R2-USB1") (pin "2") (pinfunction "2_2") (pintype "passive"))
    )
    (net (code "34") (name "Net-(J2-PadB5)") (class "Default")
      (node (ref "J2") (pin "B5") (pinfunction "B5_B5") (pintype "bidirectional"))
      (node (ref "R2-USB") (pin "1") (pinfunction "1_1") (pintype "passive"))
    )
    (net (code "35") (name "Net-(MCP73831-PROG)") (class "Default")
      (node (ref "MCP73831") (pin "5") (pinfunction "PROG_5") (pintype "input"))
      (node (ref "R2_BAT") (pin "2") (pinfunction "2_2") (pintype "passive"))
    )
    (net (code "36") (name "Net-(MCP73831-STAT)") (class "Default")
      (node (ref "MCP73831") (pin "1") (pinfunction "STAT_1") (pintype "output"))
      (node (ref "R1_BAT") (pin "1") (pinfunction "1_1") (pintype "passive"))
    )
    (net (code "37") (name "PREVGH") (class "Default")
      (node (ref "D12") (pin "1") (pinfunction "K_1") (pintype "bidirectional"))
      (node (ref "EPD_C9") (pin "1") (pinfunction "1_1") (pintype "passive"))
      (node (ref "J1") (pin "21") (pinfunction "21_21") (pintype "bidirectional"))
    )
    (net (code "38") (name "PREVGL") (class "Default")
      (node (ref "D11") (pin "2") (pinfunction "A_2") (pintype "bidirectional"))
      (node (ref "EPD_C11") (pin "1") (pinfunction "1_1") (pintype "passive"))
      (node (ref "J1") (pin "23") (pinfunction "23_23") (pintype "bidirectional"))
    )
    (net (code "39") (name "RESE") (class "Default")
      (node (ref "J1") (pin "3") (pinfunction "3_3") (pintype "bidirectional"))
      (node (ref "Q3") (pin "2") (pinfunction "S_2") (pintype "bidirectional"))
      (node (ref "R11") (pin "2") (pinfunction "2_2") (pintype "passive"))
    )
    (net (code "40") (name "RESE'") (class "Default")
      (node (ref "R1") (pin "2") (pinfunction "2_2") (pintype "passive"))
      (node (ref "R11") (pin "1") (pinfunction "1_1") (pintype "passive"))
      (node (ref "SJ1") (pin "2") (pinfunction "2_2") (pintype "passive"))
    )
    (net (code "41") (name "RESET") (class "Default")
      (node (ref "C7") (pin "1") (pinfunction "1_1") (pintype "passive"))
      (node (ref "IC1") (pin "1") (pinfunction "VOUT_1") (pintype "bidirectional"))
      (node (ref "RESET_BUTTON") (pin "3") (pinfunction "3_3") (pintype "passive"))
      (node (ref "RESET_BUTTON") (pin "4") (pinfunction "4_4") (pintype "passive"))
      (node (ref "R_RESET") (pin "2") (pinfunction "2_2") (pintype "passive"))
      (node (ref "U2") (pin "3") (pinfunction "EN_3") (pintype "input"))
    )
    (net (code "42") (name "RTC_RST") (class "Default")
      (node (ref "U2") (pin "16") (pinfunction "IO18_16") (pintype "bidirectional"))
      (node (ref "U3") (pin "4") (pinfunction "~{RST}_4") (pintype "input"))
    )
    (net (code "43") (name "RX") (class "Default")
      (node (ref "TP2") (pin "TP") (pinfunction "TP_TP") (pintype "input"))
      (node (ref "U2") (pin "24") (pinfunction "RXD0/GPIO17_24") (pintype "bidirectional"))
    )
    (net (code "44") (name "SCK") (class "Default")
      (node (ref "D4") (pin "1") (pinfunction "1_1") (pintype "passive"))
      (node (ref "J1") (pin "13") (pinfunction "13_13") (pintype "bidirectional"))
      (node (ref "J4") (pin "P5") (pinfunction "CLK_P5") (pintype "bidirectional"))
      (node (ref "R5") (pin "1") (pinfunction "1_1") (pintype "passive"))
      (node (ref "TP8") (pin "TP") (pinfunction "TP_TP") (pintype "input"))
      (node (ref "U1") (pin "6") (pinfunction "CLK_6") (pintype "input"))
      (node (ref "U2") (pin "6") (pinfunction "IO6_6") (pintype "bidirectional"))
    )
    (net (code "45") (name "SCL") (class "Default")
      (node (ref "J3") (pin "4") (pinfunction "4_4") (pintype "passive"))
      (node (ref "R2-PINH") (pin "1") (pinfunction "1_1") (pintype "passive"))
      (node (ref "SENSOR2") (pin "4") (pinfunction "SCK_4") (pintype "input"))
      (node (ref "U2") (pin "20") (pinfunction "IO22_20") (pintype "bidirectional"))
      (node (ref "U3") (pin "16") (pinfunction "SCL_16") (pintype "input"))
      (node (ref "U4") (pin "7") (pinfunction "SCL_7") (pintype "input"))
    )
    (net (code "46") (name "SDA") (class "Default")
      (node (ref "J3") (pin "3") (pinfunction "3_3") (pintype "passive"))
      (node (ref "R1_PINH") (pin "1") (pinfunction "1_1") (pintype "passive"))
      (node (ref "SENSOR2") (pin "3") (pinfunction "SDI_3") (pintype "bidirectional"))
      (node (ref "U2") (pin "19") (pinfunction "IO21_19") (pintype "bidirectional"))
      (node (ref "U3") (pin "15") (pinfunction "SDA_15") (pintype "bidirectional"))
      (node (ref "U4") (pin "8") (pinfunction "SDA_8") (pintype "bidirectional"))
    )
    (net (code "47") (name "SRC") (class "Default")
      (node (ref "C4") (pin "2") (pinfunction "2_2") (pintype "passive"))
      (node (ref "D12") (pin "2") (pinfunction "A_2") (pintype "bidirectional"))
      (node (ref "L1") (pin "1") (pinfunction "1_1") (pintype "passive"))
      (node (ref "Q3") (pin "3") (pinfunction "D_3") (pintype "bidirectional"))
    )
    (net (code "48") (name "SS_SD") (class "Default")
      (node (ref "D8") (pin "1") (pinfunction "1_1") (pintype "passive"))
      (node (ref "J4") (pin "P2") (pinfunction "CD/DAT3_P2") (pintype "bidirectional"))
      (node (ref "R8") (pin "1") (pinfunction "1_1") (pintype "passive"))
      (node (ref "U2") (pin "4") (pinfunction "IO4_4") (pintype "bidirectional"))
    )
    (net (code "49") (name "TX") (class "Default")
      (node (ref "TP1") (pin "TP") (pinfunction "TP_TP") (pintype "input"))
      (node (ref "U2") (pin "25") (pinfunction "TXD0/GPIO16_25") (pintype "bidirectional"))
    )
    (net (code "50") (name "USB_D+") (class "Default")
      (node (ref "D1") (pin "4") (pinfunction "I/O2_2_4") (pintype "bidirectional"))
      (node (ref "U2") (pin "14") (pinfunction "IO13_14") (pintype "bidirectional"))
    )
    (net (code "51") (name "USB_D-") (class "Default")
      (node (ref "D1") (pin "6") (pinfunction "I/O1_2_6") (pintype "bidirectional"))
      (node (ref "U2") (pin "13") (pinfunction "IO12_13") (pintype "bidirectional"))
    )
    (net (code "52") (name "VBAT") (class "Default")
      (node (ref "C2_BAT") (pin "1") (pinfunction "1_1") (pintype "passive"))
      (node (ref "MCP73831") (pin "3") (pinfunction "VBAT_3") (pintype "power_in"))
      (node (ref "Q1") (pin "3") (pinfunction "D_3") (pintype "bidirectional"))
      (node (ref "TP3") (pin "TP") (pinfunction "TP_TP") (pintype "input"))
      (node (ref "U4") (pin "2") (pinfunction "CELL_2") (pintype "power_in"))
      (node (ref "U4") (pin "3") (pinfunction "VDD_3") (pintype "power_in"))
    )
    (net (code "53") (name "VBUS") (class "Default")
      (node (ref "C1_BAT") (pin "1") (pinfunction "1_1") (pintype "passive"))
      (node (ref "C4_USB") (pin "1") (pinfunction "1_1") (pintype "passive"))
      (node (ref "C5_USB") (pin "1") (pinfunction "1_1") (pintype "passive"))
      (node (ref "CHG_LED") (pin "A") (pinfunction "A_A") (pintype "passive"))
      (node (ref "D1") (pin "2") (pinfunction "GND_2") (pintype "bidirectional"))
      (node (ref "D9") (pin "2") (pinfunction "ANODE_2") (pintype "bidirectional"))
      (node (ref "MCP73831") (pin "4") (pinfunction "VIN_4") (pintype "power_in"))
      (node (ref "Q1") (pin "1") (pinfunction "G_1") (pintype "bidirectional"))
      (node (ref "R1_PWRUSB") (pin "2") (pinfunction "2_2") (pintype "passive"))
      (node (ref "R2") (pin "2") (pinfunction "2_2") (pintype "passive"))
      (node (ref "TP14") (pin "TP") (pinfunction "TP_TP") (pintype "input"))
    )
    (net (code "54") (name "VRTC") (class "Default")
      (node (ref "C8") (pin "1") (pinfunction "1_1") (pintype "passive"))
      (node (ref "CPH3225A") (pin "1") (pinfunction "1_1") (pintype "passive"))
      (node (ref "R_CAPACITOR") (pin "2") (pinfunction "2_2") (pintype "passive"))
      (node (ref "U3") (pin "14") (pinfunction "VBAT_14") (pintype "power_in"))
    )
    (net (code "55") (name "VUSB") (class "Default")
      (node (ref "J2") (pin "A4") (pinfunction "A4_A4") (pintype "bidirectional"))
      (node (ref "J2") (pin "A9") (pinfunction "A9_A9") (pintype "bidirectional"))
      (node (ref "J2") (pin "B4") (pinfunction "B4_B4") (pintype "bidirectional"))
      (node (ref "J2") (pin "B9") (pinfunction "B9_B9") (pintype "bidirectional"))
      (node (ref "R2") (pin "1") (pinfunction "1_1") (pintype "passive"))
    )
    (net (code "56") (name "unconnected-(IC1-NC-Pad4)") (class "Default")
      (node (ref "IC1") (pin "4") (pinfunction "NC_4") (pintype "no_connect"))
    )
    (net (code "57") (name "unconnected-(IC4-NC-Pad4)") (class "Default")
      (node (ref "IC4") (pin "4") (pinfunction "NC_4") (pintype "no_connect"))
    )
    (net (code "58") (name "unconnected-(J1-Pad1)") (class "Default")
      (node (ref "J1") (pin "1") (pinfunction "1_1") (pintype "bidirectional"))
    )
    (net (code "59") (name "unconnected-(J1-Pad6)") (class "Default")
      (node (ref "J1") (pin "6") (pinfunction "6_6") (pintype "bidirectional"))
    )
    (net (code "60") (name "unconnected-(J1-Pad7)") (class "Default")
      (node (ref "J1") (pin "7") (pinfunction "7_7") (pintype "bidirectional"))
    )
    (net (code "61") (name "unconnected-(J2-PadA8)") (class "Default")
      (node (ref "J2") (pin "A8") (pinfunction "A8_A8") (pintype "bidirectional"))
    )
    (net (code "62") (name "unconnected-(J2-PadB8)") (class "Default")
      (node (ref "J2") (pin "B8") (pinfunction "B8_B8") (pintype "bidirectional"))
    )
    (net (code "63") (name "unconnected-(J4-DAT1-PadP8)") (class "Default")
      (node (ref "J4") (pin "P8") (pinfunction "DAT1_P8") (pintype "bidirectional"))
    )
    (net (code "64") (name "unconnected-(J4-DAT2-PadP1)") (class "Default")
      (node (ref "J4") (pin "P1") (pinfunction "DAT2_P1") (pintype "bidirectional"))
    )
    (net (code "65") (name "unconnected-(J4-DETECTION_1-PadS1)") (class "Default")
      (node (ref "J4") (pin "S1") (pinfunction "DETECTION_1_S1") (pintype "bidirectional"))
    )
    (net (code "66") (name "unconnected-(J4-DETECTION_2-PadS2)") (class "Default")
      (node (ref "J4") (pin "S2") (pinfunction "DETECTION_2_S2") (pintype "bidirectional"))
    )
    (net (code "67") (name "unconnected-(U2-NC-Pad22)") (class "Default")
      (node (ref "U2") (pin "22") (pinfunction "NC_22") (pintype "no_connect"))
    )
    (net (code "68") (name "unconnected-(U4-~{ALERT}-Pad5)") (class "Default")
      (node (ref "U4") (pin "5") (pinfunction "~{ALERT}_5") (pintype "output"))
    )
  )
)
